# 03_-_External_Connectors.net
KiCad netlist of a schematic drawn in Altium Designer
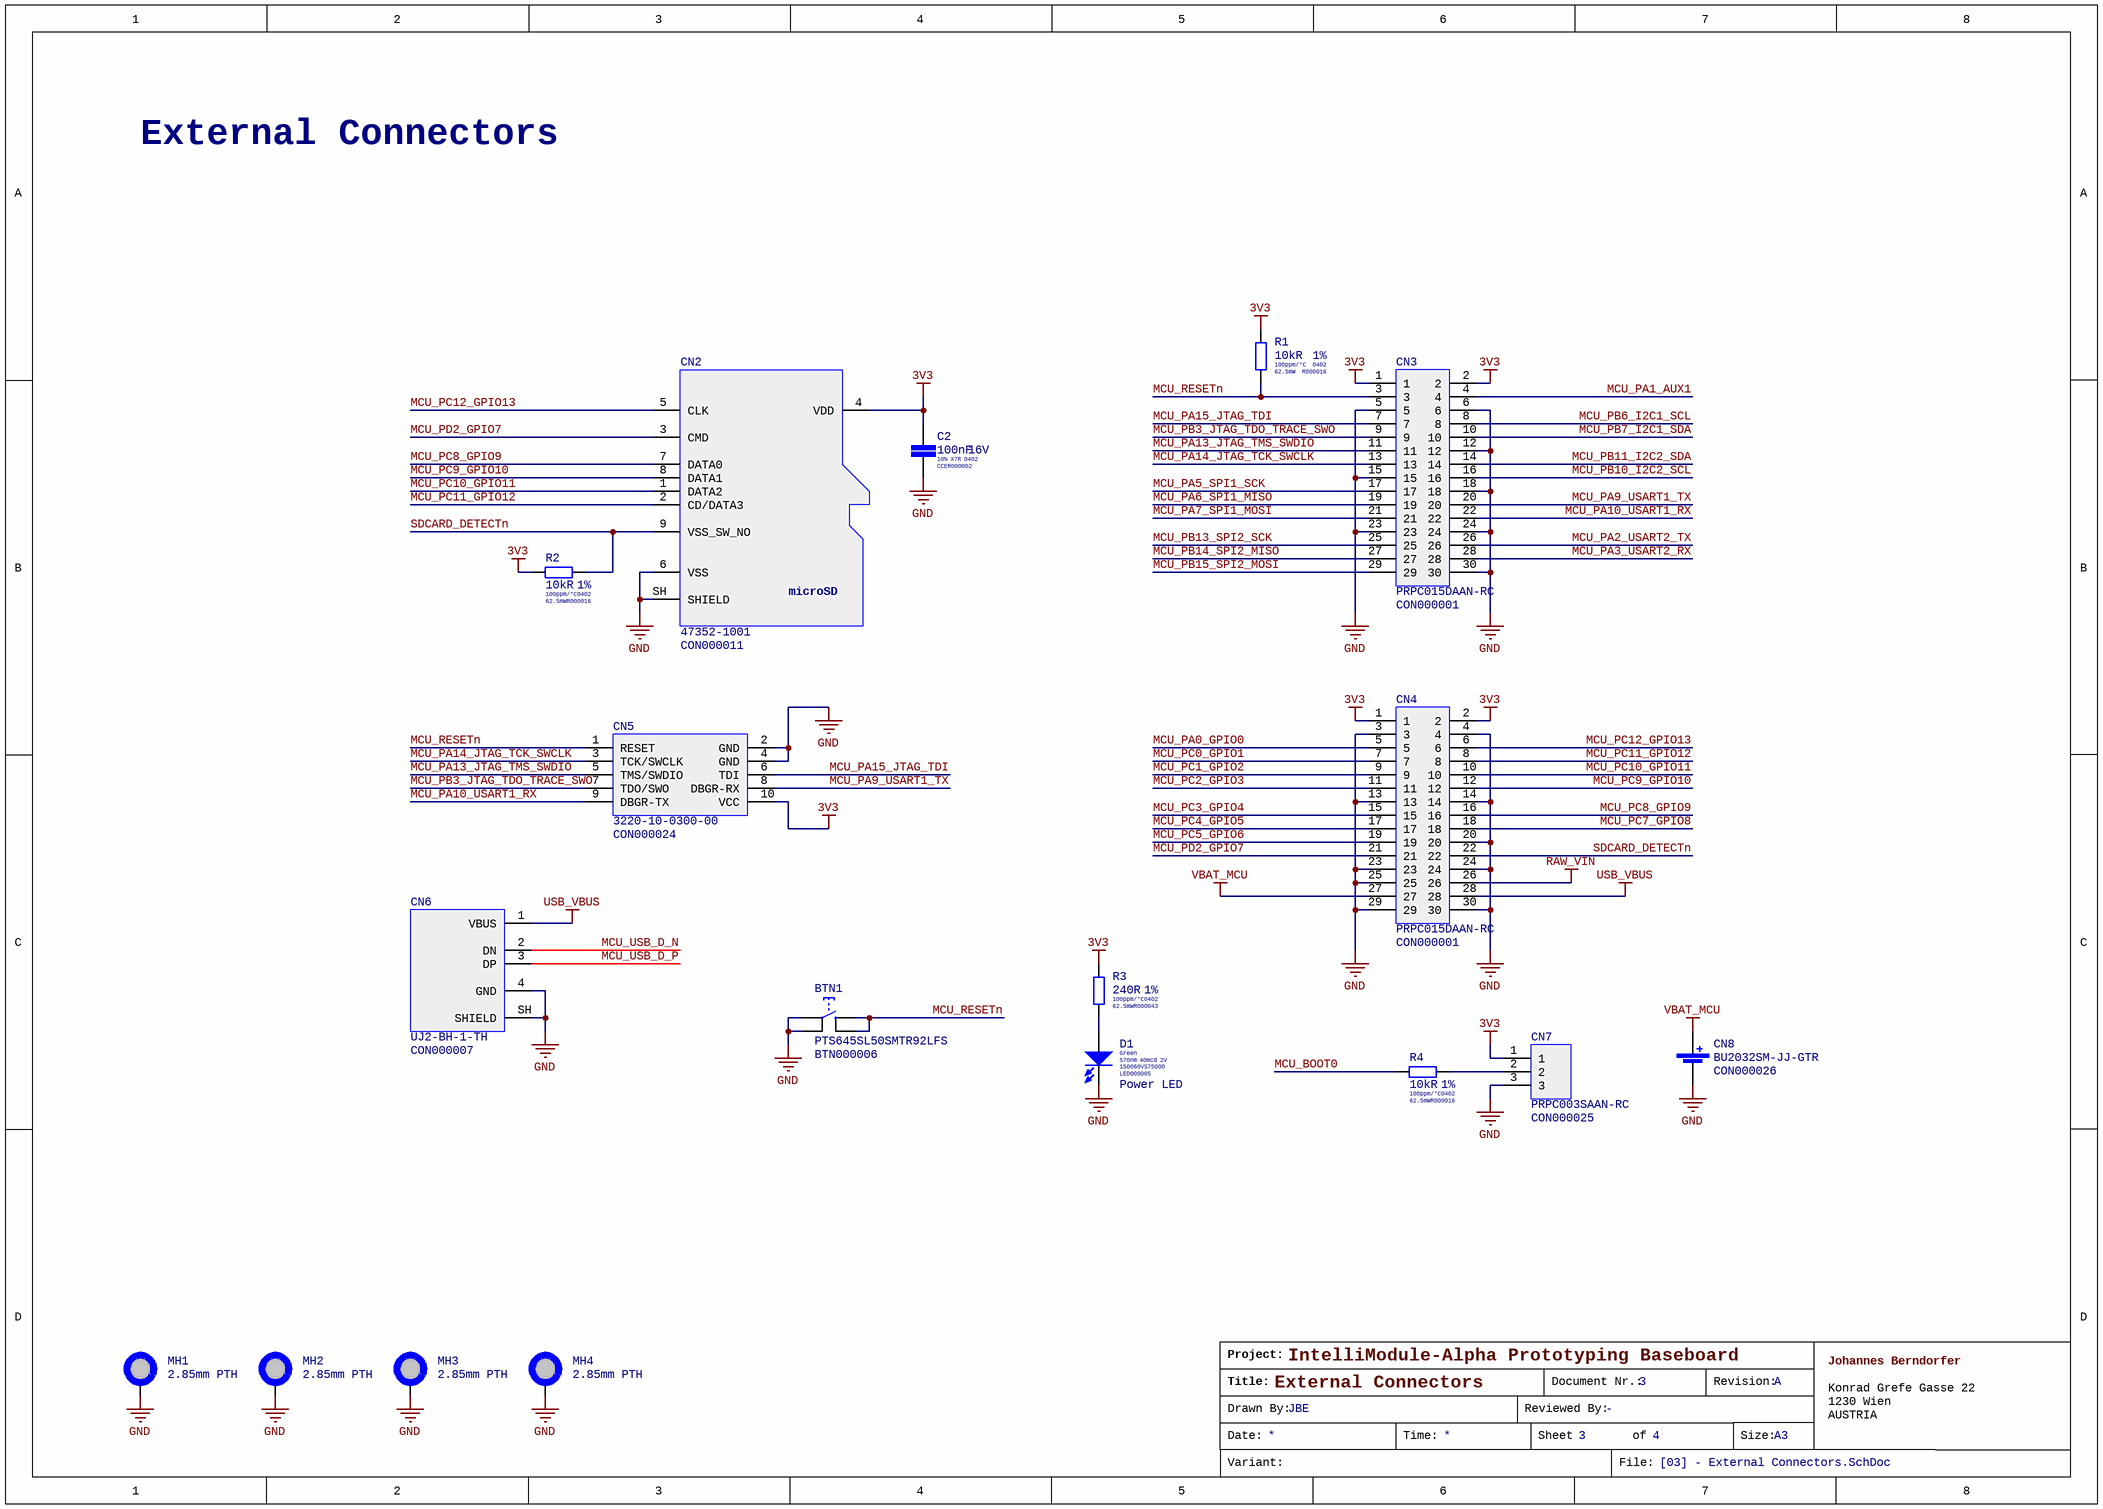
[diagram p0: [03] - External Connectors.SchDoc]

(export (version "E")
  (design (tool "Eeschema 10.0.6"))
  (components
    (comp (ref "BTN1")
      (value "PTS645SL50SMTR92LFS")
      (footprint "BTN-SMD-PTS645-CK")
      (description "BTN TACT SPST-NO 12V 50mA SMD BLACK")
      (fields (field (name "MANUFACTURER") "ITT C&K") (field (name "INTERNAL PART NUMBER") "BTN000006"))
      (libsource (lib "Altium_Lib_Standard") (part "PTS645SL50SMTR92LFS"))
    )
    (comp (ref "C2")
      (value "100nF 16V")
      (footprint "CAP-SMD-0402-0.55MM-IPC-MED")
      (description "CAP CER 100N 16V X7R 10% SMD 0402 125C SAMSUNG")
      (fields
        (field (name "VOLTAGE") "16V")
        (field (name "TOLERANCE") "10%")
        (field (name "INTERNAL PART NUMBER") "CCER000002")
        (field (name "VOLTAGE RATING (DC)") "16V")
        (field (name "DIELECTRIC") "X7R")
        (field (name "CASE/PACKAGE") "0402")
        (field (name "CAPACITANCE") "100nF")
      )
      (libsource (lib "Altium_Lib_Standard") (part "CL05B104KO5NNNC"))
    )
    (comp (ref "CN2")
      (value "47352-1001")
      (footprint "CON-SMD-MICROSD-PUSHPULL-9POS-0473521001-MOLEX")
      (description "CON MICROSD SMD PUSH PUSH TYPE VSS SW")
      (fields (field (name "INTERNAL PART NUMBER") "CON000011"))
      (libsource (lib "Altium_Lib_Standard") (part "MOLEX 47352-1001"))
    )
    (comp (ref "CN3")
      (value "PRPC015DAAN-RC")
      (footprint "CON-THT-PINHEADER-2.54MM-30POS-2X15")
      (description "CON PINHDR 2MM54 2X15")
      (fields (field (name "MANUFACTURER") "Sullins") (field (name "INTERNAL PART NUMBER") "CON000001"))
      (libsource (lib "Altium_Lib_Standard") (part "PRPC015DAAN-RC"))
    )
    (comp (ref "CN4")
      (value "PRPC015DAAN-RC")
      (footprint "CON-THT-PINHEADER-2.54MM-30POS-2X15")
      (description "CON PINHDR 2MM54 2X15")
      (fields (field (name "MANUFACTURER") "Sullins") (field (name "INTERNAL PART NUMBER") "CON000001"))
      (libsource (lib "Altium_Lib_Standard") (part "PRPC015DAAN-RC"))
    )
    (comp (ref "CN5")
      (value "3220-10-0300-00")
      (footprint "CON-SMD-PINHEADER-SHIELDED-1.27MM-10POS-2X5-3220-10-0300-00-CNC-TECH")
      (description "CON PINHDR SMD 1.27MM SHIELDED KEYED CNC TECH 10POS")
      (fields (field (name "INTERNAL PART NUMBER") "CON000024"))
      (libsource (lib "Altium_Lib_Standard") (part "3220-10-0300-00"))
    )
    (comp (ref "CN6")
      (value "UJ2-BH-1-TH")
      (footprint "CON-THT-USB-B-4POS-UJ2-BH-1-TH-CUI")
      (description "CON USB 2.0 B THROUGH HOLE WHTE INSULATOR")
      (fields (field (name "MANUFACTURER") "CUI") (field (name "INTERNAL PART NUMBER") "CON000007"))
      (libsource (lib "Altium_Lib_Standard") (part "UJ2-BH-1-TH"))
    )
    (comp (ref "CN7")
      (value "PRPC003SAAN-RC")
      (footprint "CON-THT-PINHEADER-2.54MM-3POS-1X3")
      (description "CON PINHDR 2.54MM 1x03")
      (fields (field (name "MANUFACTURER") "Sullins") (field (name "INTERNAL PART NUMBER") "CON000025"))
      (libsource (lib "Altium_Lib_Standard") (part "PRPC003SAAN-RC"))
    )
    (comp (ref "CN8")
      (value "BU2032SM-JJ-GTR")
      (footprint "CON-SMD-BU2032SM-JJ-GTR")
      (description "CON BATTERY HOLDER 2032 COINCELL SMD")
      (fields
        (field (name "MANUFACTURER") "Memory Protection Devices")
        (field (name "INTERNAL PART NUMBER") "CON000026")
      )
      (libsource (lib "Altium_Lib_Standard") (part "BU2032SM-JJ-GTR"))
    )
    (comp (ref "D1")
      (value "150060VS75000")
      (footprint "LED-SMD-0603")
      (description "LED GREEN570NM SMD 0603 2V 20mA 40mcd")
      (fields
        (field (name "MANUFACTURER") "Wurth Electronics")
        (field (name "LUMINOUS INTENSITY") "40mcd")
        (field (name "FORWARD VOLTAGE") "2V")
        (field (name "COLOR") "Green")
        (field (name "MANUFACTURER PART NUMBER") "150060VS75000")
        (field (name "WAVELENGTH") "570nm")
        (field (name "INTERNAL PART NUMBER") "LED000005")
      )
      (libsource (lib "Altium_Lib_Standard") (part "150060VS75000"))
    )
    (comp (ref "MH1")
      (value "2.85mm PTH")
      (footprint "MECH-HOLE-PTH-2.85MM-5.4MM")
      (description "2.85mm Diameter 5.4mm Pad Plated Through Hole")
      (libsource (lib "Altium_Lib_Standard") (part "MECH-HOLE-PTH-2.85MM-5.4MM"))
    )
    (comp (ref "MH2")
      (value "2.85mm PTH")
      (footprint "MECH-HOLE-PTH-2.85MM-5.4MM")
      (description "2.85mm Diameter 5.4mm Pad Plated Through Hole")
      (libsource (lib "Altium_Lib_Standard") (part "MECH-HOLE-PTH-2.85MM-5.4MM"))
    )
    (comp (ref "MH3")
      (value "2.85mm PTH")
      (footprint "MECH-HOLE-PTH-2.85MM-5.4MM")
      (description "2.85mm Diameter 5.4mm Pad Plated Through Hole")
      (libsource (lib "Altium_Lib_Standard") (part "MECH-HOLE-PTH-2.85MM-5.4MM"))
    )
    (comp (ref "MH4")
      (value "2.85mm PTH")
      (footprint "MECH-HOLE-PTH-2.85MM-5.4MM")
      (description "2.85mm Diameter 5.4mm Pad Plated Through Hole")
      (libsource (lib "Altium_Lib_Standard") (part "MECH-HOLE-PTH-2.85MM-5.4MM"))
    )
    (comp (ref "R1")
      (value "10kR 1%")
      (footprint "RES-SMD-0402-0.4MM-IPC-MED")
      (description "RES 10K 1% 1/16W SMD 0402 YAEGO")
      (fields
        (field (name "MANUFACTURER") "Yageo")
        (field (name "MANUFACTURER PART NUMBER") "RC0402FR-0710KL")
        (field (name "TOLERANCE") "1%")
        (field (name "TEMPERATURE COEFFICIENT") "100ppm/°C")
        (field (name "RESISTANCE") "10kR")
        (field (name "POWER RATING") "62.5mW")
        (field (name "CASE CODE (IMPERIAL)") "0402")
        (field (name "INTERNAL PART NUMBER") "R000016")
      )
      (libsource (lib "Altium_Lib_Standard") (part "RC0402FR-0710KL"))
    )
    (comp (ref "R2")
      (value "10kR 1%")
      (footprint "RES-SMD-0402-0.4MM-IPC-MED")
      (description "RES 10K 1% 1/16W SMD 0402 YAEGO")
      (fields
        (field (name "MANUFACTURER") "Yageo")
        (field (name "MANUFACTURER PART NUMBER") "RC0402FR-0710KL")
        (field (name "TOLERANCE") "1%")
        (field (name "TEMPERATURE COEFFICIENT") "100ppm/°C")
        (field (name "RESISTANCE") "10kR")
        (field (name "POWER RATING") "62.5mW")
        (field (name "CASE CODE (IMPERIAL)") "0402")
        (field (name "INTERNAL PART NUMBER") "R000016")
      )
      (libsource (lib "Altium_Lib_Standard") (part "RC0402FR-0710KL"))
    )
    (comp (ref "R3")
      (value "240R 1%")
      (footprint "RES-SMD-0402-0.4MM-IPC-MED")
      (description "RES 240R 1% 1/16W SMD 0402 YAGEO")
      (fields
        (field (name "MANUFACTURER") "Yageo Phycomp")
        (field (name "MANUFACTURER PART NUMBER") "RC0402FR-07240RL")
        (field (name "RESISTANCE") "240R")
        (field (name "TOLERANCE") "1%")
        (field (name "TEMPERATURE COEFFICIENT") "100ppm/°C")
        (field (name "POWER RATING") "62.5mW")
        (field (name "CASE/PACKAGE") "0402")
        (field (name "INTERNAL PART NUMBER") "R000043")
      )
      (libsource (lib "Altium_Lib_Standard") (part "RC0402FR-07240RL"))
    )
    (comp (ref "R4")
      (value "10kR 1%")
      (footprint "RES-SMD-0402-0.4MM-IPC-MED")
      (description "RES 10K 1% 1/16W SMD 0402 YAEGO")
      (fields
        (field (name "MANUFACTURER") "Yageo")
        (field (name "MANUFACTURER PART NUMBER") "RC0402FR-0710KL")
        (field (name "TOLERANCE") "1%")
        (field (name "TEMPERATURE COEFFICIENT") "100ppm/°C")
        (field (name "RESISTANCE") "10kR")
        (field (name "POWER RATING") "62.5mW")
        (field (name "CASE CODE (IMPERIAL)") "0402")
        (field (name "INTERNAL PART NUMBER") "R000016")
      )
      (libsource (lib "Altium_Lib_Standard") (part "RC0402FR-0710KL"))
    )
  )
  (nets
    (net (code "1") (name "/MCU_BOOT0") (class "Default")
      (node (ref "R4") (pin "1") (pinfunction "1_1") (pintype "passive"))
    )
    (net (code "2") (name "/MCU_PA0_GPIO0") (class "Default")
      (node (ref "CN4") (pin "5") (pinfunction "5_5") (pintype "passive"))
    )
    (net (code "3") (name "/MCU_PA1_AUX1") (class "Default")
      (node (ref "CN3") (pin "4") (pinfunction "4_4") (pintype "passive"))
    )
    (net (code "4") (name "/MCU_PA2_USART2_TX") (class "Default")
      (node (ref "CN3") (pin "26") (pinfunction "26_26") (pintype "passive"))
    )
    (net (code "5") (name "/MCU_PA3_USART2_RX") (class "Default")
      (node (ref "CN3") (pin "28") (pinfunction "28_28") (pintype "passive"))
    )
    (net (code "6") (name "/MCU_PA5_SPI1_SCK") (class "Default")
      (node (ref "CN3") (pin "17") (pinfunction "17_17") (pintype "passive"))
    )
    (net (code "7") (name "/MCU_PA6_SPI1_MISO") (class "Default")
      (node (ref "CN3") (pin "19") (pinfunction "19_19") (pintype "passive"))
    )
    (net (code "8") (name "/MCU_PA7_SPI1_MOSI") (class "Default")
      (node (ref "CN3") (pin "21") (pinfunction "21_21") (pintype "passive"))
    )
    (net (code "9") (name "/MCU_PA9_USART1_TX") (class "Default")
      (node (ref "CN3") (pin "20") (pinfunction "20_20") (pintype "passive"))
      (node (ref "CN5") (pin "8") (pinfunction "DBGR-RX_8") (pintype "passive"))
    )
    (net (code "10") (name "/MCU_PA10_USART1_RX") (class "Default")
      (node (ref "CN3") (pin "22") (pinfunction "22_22") (pintype "passive"))
      (node (ref "CN5") (pin "9") (pinfunction "DBGR-TX_9") (pintype "passive"))
    )
    (net (code "11") (name "/MCU_PA13_JTAG_TMS_SWDIO") (class "Default")
      (node (ref "CN3") (pin "11") (pinfunction "11_11") (pintype "passive"))
      (node (ref "CN5") (pin "5") (pinfunction "TMS/SWDIO_5") (pintype "passive"))
    )
    (net (code "12") (name "/MCU_PA14_JTAG_TCK_SWCLK") (class "Default")
      (node (ref "CN3") (pin "13") (pinfunction "13_13") (pintype "passive"))
      (node (ref "CN5") (pin "3") (pinfunction "TCK/SWCLK_3") (pintype "passive"))
    )
    (net (code "13") (name "/MCU_PA15_JTAG_TDI") (class "Default")
      (node (ref "CN3") (pin "7") (pinfunction "7_7") (pintype "passive"))
      (node (ref "CN5") (pin "6") (pinfunction "TDI_6") (pintype "passive"))
    )
    (net (code "14") (name "/MCU_PB3_JTAG_TDO_TRACE_SWO") (class "Default")
      (node (ref "CN3") (pin "9") (pinfunction "9_9") (pintype "passive"))
      (node (ref "CN5") (pin "7") (pinfunction "TDO/SWO_7") (pintype "passive"))
    )
    (net (code "15") (name "/MCU_PB6_I2C1_SCL") (class "Default")
      (node (ref "CN3") (pin "8") (pinfunction "8_8") (pintype "passive"))
    )
    (net (code "16") (name "/MCU_PB7_I2C1_SDA") (class "Default")
      (node (ref "CN3") (pin "10") (pinfunction "10_10") (pintype "passive"))
    )
    (net (code "17") (name "/MCU_PB10_I2C2_SCL") (class "Default")
      (node (ref "CN3") (pin "16") (pinfunction "16_16") (pintype "passive"))
    )
    (net (code "18") (name "/MCU_PB11_I2C2_SDA") (class "Default")
      (node (ref "CN3") (pin "14") (pinfunction "14_14") (pintype "passive"))
    )
    (net (code "19") (name "/MCU_PB13_SPI2_SCK") (class "Default")
      (node (ref "CN3") (pin "25") (pinfunction "25_25") (pintype "passive"))
    )
    (net (code "20") (name "/MCU_PB14_SPI2_MISO") (class "Default")
      (node (ref "CN3") (pin "27") (pinfunction "27_27") (pintype "passive"))
    )
    (net (code "21") (name "/MCU_PB15_SPI2_MOSI") (class "Default")
      (node (ref "CN3") (pin "29") (pinfunction "29_29") (pintype "passive"))
    )
    (net (code "22") (name "/MCU_PC0_GPIO1") (class "Default")
      (node (ref "CN4") (pin "7") (pinfunction "7_7") (pintype "passive"))
    )
    (net (code "23") (name "/MCU_PC1_GPIO2") (class "Default")
      (node (ref "CN4") (pin "9") (pinfunction "9_9") (pintype "passive"))
    )
    (net (code "24") (name "/MCU_PC2_GPIO3") (class "Default")
      (node (ref "CN4") (pin "11") (pinfunction "11_11") (pintype "passive"))
    )
    (net (code "25") (name "/MCU_PC3_GPIO4") (class "Default")
      (node (ref "CN4") (pin "15") (pinfunction "15_15") (pintype "passive"))
    )
    (net (code "26") (name "/MCU_PC4_GPIO5") (class "Default")
      (node (ref "CN4") (pin "17") (pinfunction "17_17") (pintype "passive"))
    )
    (net (code "27") (name "/MCU_PC5_GPIO6") (class "Default")
      (node (ref "CN4") (pin "19") (pinfunction "19_19") (pintype "passive"))
    )
    (net (code "28") (name "/MCU_PC7_GPIO8") (class "Default")
      (node (ref "CN4") (pin "18") (pinfunction "18_18") (pintype "passive"))
    )
    (net (code "29") (name "/MCU_PC8_GPIO9") (class "Default")
      (node (ref "CN2") (pin "7") (pinfunction "DATA0_7") (pintype "passive"))
      (node (ref "CN4") (pin "16") (pinfunction "16_16") (pintype "passive"))
    )
    (net (code "30") (name "/MCU_PC9_GPIO10") (class "Default")
      (node (ref "CN2") (pin "8") (pinfunction "DATA1_8") (pintype "passive"))
      (node (ref "CN4") (pin "12") (pinfunction "12_12") (pintype "passive"))
    )
    (net (code "31") (name "/MCU_PC10_GPIO11") (class "Default")
      (node (ref "CN2") (pin "1") (pinfunction "DATA2_1") (pintype "passive"))
      (node (ref "CN4") (pin "10") (pinfunction "10_10") (pintype "passive"))
    )
    (net (code "32") (name "/MCU_PC11_GPIO12") (class "Default")
      (node (ref "CN2") (pin "2") (pinfunction "CD/DATA3_2") (pintype "passive"))
      (node (ref "CN4") (pin "8") (pinfunction "8_8") (pintype "passive"))
    )
    (net (code "33") (name "/MCU_PC12_GPIO13") (class "Default")
      (node (ref "CN2") (pin "5") (pinfunction "CLK_5") (pintype "passive"))
      (node (ref "CN4") (pin "6") (pinfunction "6_6") (pintype "passive"))
    )
    (net (code "34") (name "/MCU_PD2_GPIO7") (class "Default")
      (node (ref "CN2") (pin "3") (pinfunction "CMD_3") (pintype "passive"))
      (node (ref "CN4") (pin "21") (pinfunction "21_21") (pintype "passive"))
    )
    (net (code "35") (name "/MCU_RESETn") (class "Default")
      (node (ref "BTN1") (pin "3") (pinfunction "3_3") (pintype "passive"))
      (node (ref "BTN1") (pin "4") (pinfunction "4_4") (pintype "passive"))
      (node (ref "CN3") (pin "3") (pinfunction "3_3") (pintype "passive"))
      (node (ref "CN5") (pin "1") (pinfunction "RESET_1") (pintype "passive"))
      (node (ref "R1") (pin "2") (pinfunction "2_2") (pintype "passive"))
    )
    (net (code "36") (name "/MCU_USB_D_N") (class "Default")
      (node (ref "CN6") (pin "2") (pinfunction "DN_2") (pintype "passive"))
    )
    (net (code "37") (name "/MCU_USB_D_P") (class "Default")
      (node (ref "CN6") (pin "3") (pinfunction "DP_3") (pintype "passive"))
    )
    (net (code "38") (name "/SDCARD_DETECTn") (class "Default")
      (node (ref "CN2") (pin "9") (pinfunction "VSS_SW_NO_9") (pintype "passive"))
      (node (ref "CN4") (pin "22") (pinfunction "22_22") (pintype "passive"))
      (node (ref "R2") (pin "2") (pinfunction "2_2") (pintype "passive"))
    )
    (net (code "39") (name "3V3") (class "Default")
      (node (ref "C2") (pin "1") (pinfunction "1_1") (pintype "passive"))
      (node (ref "CN2") (pin "4") (pinfunction "VDD_4") (pintype "passive"))
      (node (ref "CN3") (pin "1") (pinfunction "1_1") (pintype "passive"))
      (node (ref "CN3") (pin "2") (pinfunction "2_2") (pintype "passive"))
      (node (ref "CN4") (pin "1") (pinfunction "1_1") (pintype "passive"))
      (node (ref "CN4") (pin "2") (pinfunction "2_2") (pintype "passive"))
      (node (ref "CN5") (pin "10") (pinfunction "VCC_10") (pintype "passive"))
      (node (ref "CN7") (pin "1") (pinfunction "1_1") (pintype "passive"))
      (node (ref "R1") (pin "1") (pinfunction "1_1") (pintype "passive"))
      (node (ref "R2") (pin "1") (pinfunction "1_1") (pintype "passive"))
      (node (ref "R3") (pin "1") (pinfunction "1_1") (pintype "passive"))
    )
    (net (code "40") (name "GND") (class "Default")
      (node (ref "BTN1") (pin "1") (pinfunction "1_1") (pintype "passive"))
      (node (ref "BTN1") (pin "2") (pinfunction "2_2") (pintype "passive"))
      (node (ref "C2") (pin "2") (pinfunction "2_2") (pintype "passive"))
      (node (ref "CN2") (pin "6") (pinfunction "VSS_6") (pintype "passive"))
      (node (ref "CN2") (pin "SH") (pinfunction "SHIELD_SH") (pintype "passive"))
      (node (ref "CN3") (pin "12") (pinfunction "12_12") (pintype "passive"))
      (node (ref "CN3") (pin "15") (pinfunction "15_15") (pintype "passive"))
      (node (ref "CN3") (pin "18") (pinfunction "18_18") (pintype "passive"))
      (node (ref "CN3") (pin "23") (pinfunction "23_23") (pintype "passive"))
      (node (ref "CN3") (pin "24") (pinfunction "24_24") (pintype "passive"))
      (node (ref "CN3") (pin "30") (pinfunction "30_30") (pintype "passive"))
      (node (ref "CN3") (pin "5") (pinfunction "5_5") (pintype "passive"))
      (node (ref "CN3") (pin "6") (pinfunction "6_6") (pintype "passive"))
      (node (ref "CN4") (pin "13") (pinfunction "13_13") (pintype "passive"))
      (node (ref "CN4") (pin "14") (pinfunction "14_14") (pintype "passive"))
      (node (ref "CN4") (pin "20") (pinfunction "20_20") (pintype "passive"))
      (node (ref "CN4") (pin "23") (pinfunction "23_23") (pintype "passive"))
      (node (ref "CN4") (pin "24") (pinfunction "24_24") (pintype "passive"))
      (node (ref "CN4") (pin "25") (pinfunction "25_25") (pintype "passive"))
      (node (ref "CN4") (pin "29") (pinfunction "29_29") (pintype "passive"))
      (node (ref "CN4") (pin "3") (pinfunction "3_3") (pintype "passive"))
      (node (ref "CN4") (pin "30") (pinfunction "30_30") (pintype "passive"))
      (node (ref "CN4") (pin "4") (pinfunction "4_4") (pintype "passive"))
      (node (ref "CN5") (pin "2") (pinfunction "GND_2") (pintype "passive"))
      (node (ref "CN5") (pin "4") (pinfunction "GND_4") (pintype "passive"))
      (node (ref "CN6") (pin "4") (pinfunction "GND_4") (pintype "passive"))
      (node (ref "CN6") (pin "SH") (pinfunction "SHIELD_SH") (pintype "passive"))
      (node (ref "CN7") (pin "3") (pinfunction "3_3") (pintype "passive"))
      (node (ref "CN8") (pin "2") (pinfunction "2_2") (pintype "passive"))
      (node (ref "D1") (pin "1") (pinfunction "1_1") (pintype "passive"))
      (node (ref "MH1") (pin "1") (pinfunction "1_1") (pintype "passive"))
      (node (ref "MH2") (pin "1") (pinfunction "1_1") (pintype "passive"))
      (node (ref "MH3") (pin "1") (pinfunction "1_1") (pintype "passive"))
      (node (ref "MH4") (pin "1") (pinfunction "1_1") (pintype "passive"))
    )
    (net (code "41") (name "Net-(CN7-Pad2)") (class "Default")
      (node (ref "CN7") (pin "2") (pinfunction "2_2") (pintype "passive"))
      (node (ref "R4") (pin "2") (pinfunction "2_2") (pintype "passive"))
    )
    (net (code "42") (name "Net-(D1-Pad2)") (class "Default")
      (node (ref "D1") (pin "2") (pinfunction "2_2") (pintype "passive"))
      (node (ref "R3") (pin "2") (pinfunction "2_2") (pintype "passive"))
    )
    (net (code "43") (name "RAW_VIN") (class "Default")
      (node (ref "CN4") (pin "26") (pinfunction "26_26") (pintype "passive"))
    )
    (net (code "44") (name "USB_VBUS") (class "Default")
      (node (ref "CN4") (pin "28") (pinfunction "28_28") (pintype "passive"))
      (node (ref "CN6") (pin "1") (pinfunction "VBUS_1") (pintype "passive"))
    )
    (net (code "45") (name "VBAT_MCU") (class "Default")
      (node (ref "CN4") (pin "27") (pinfunction "27_27") (pintype "passive"))
      (node (ref "CN8") (pin "1") (pinfunction "1_1") (pintype "passive"))
    )
  )
)
